# eth_part.net
KiCad netlist of a schematic drawn in Altium Designer
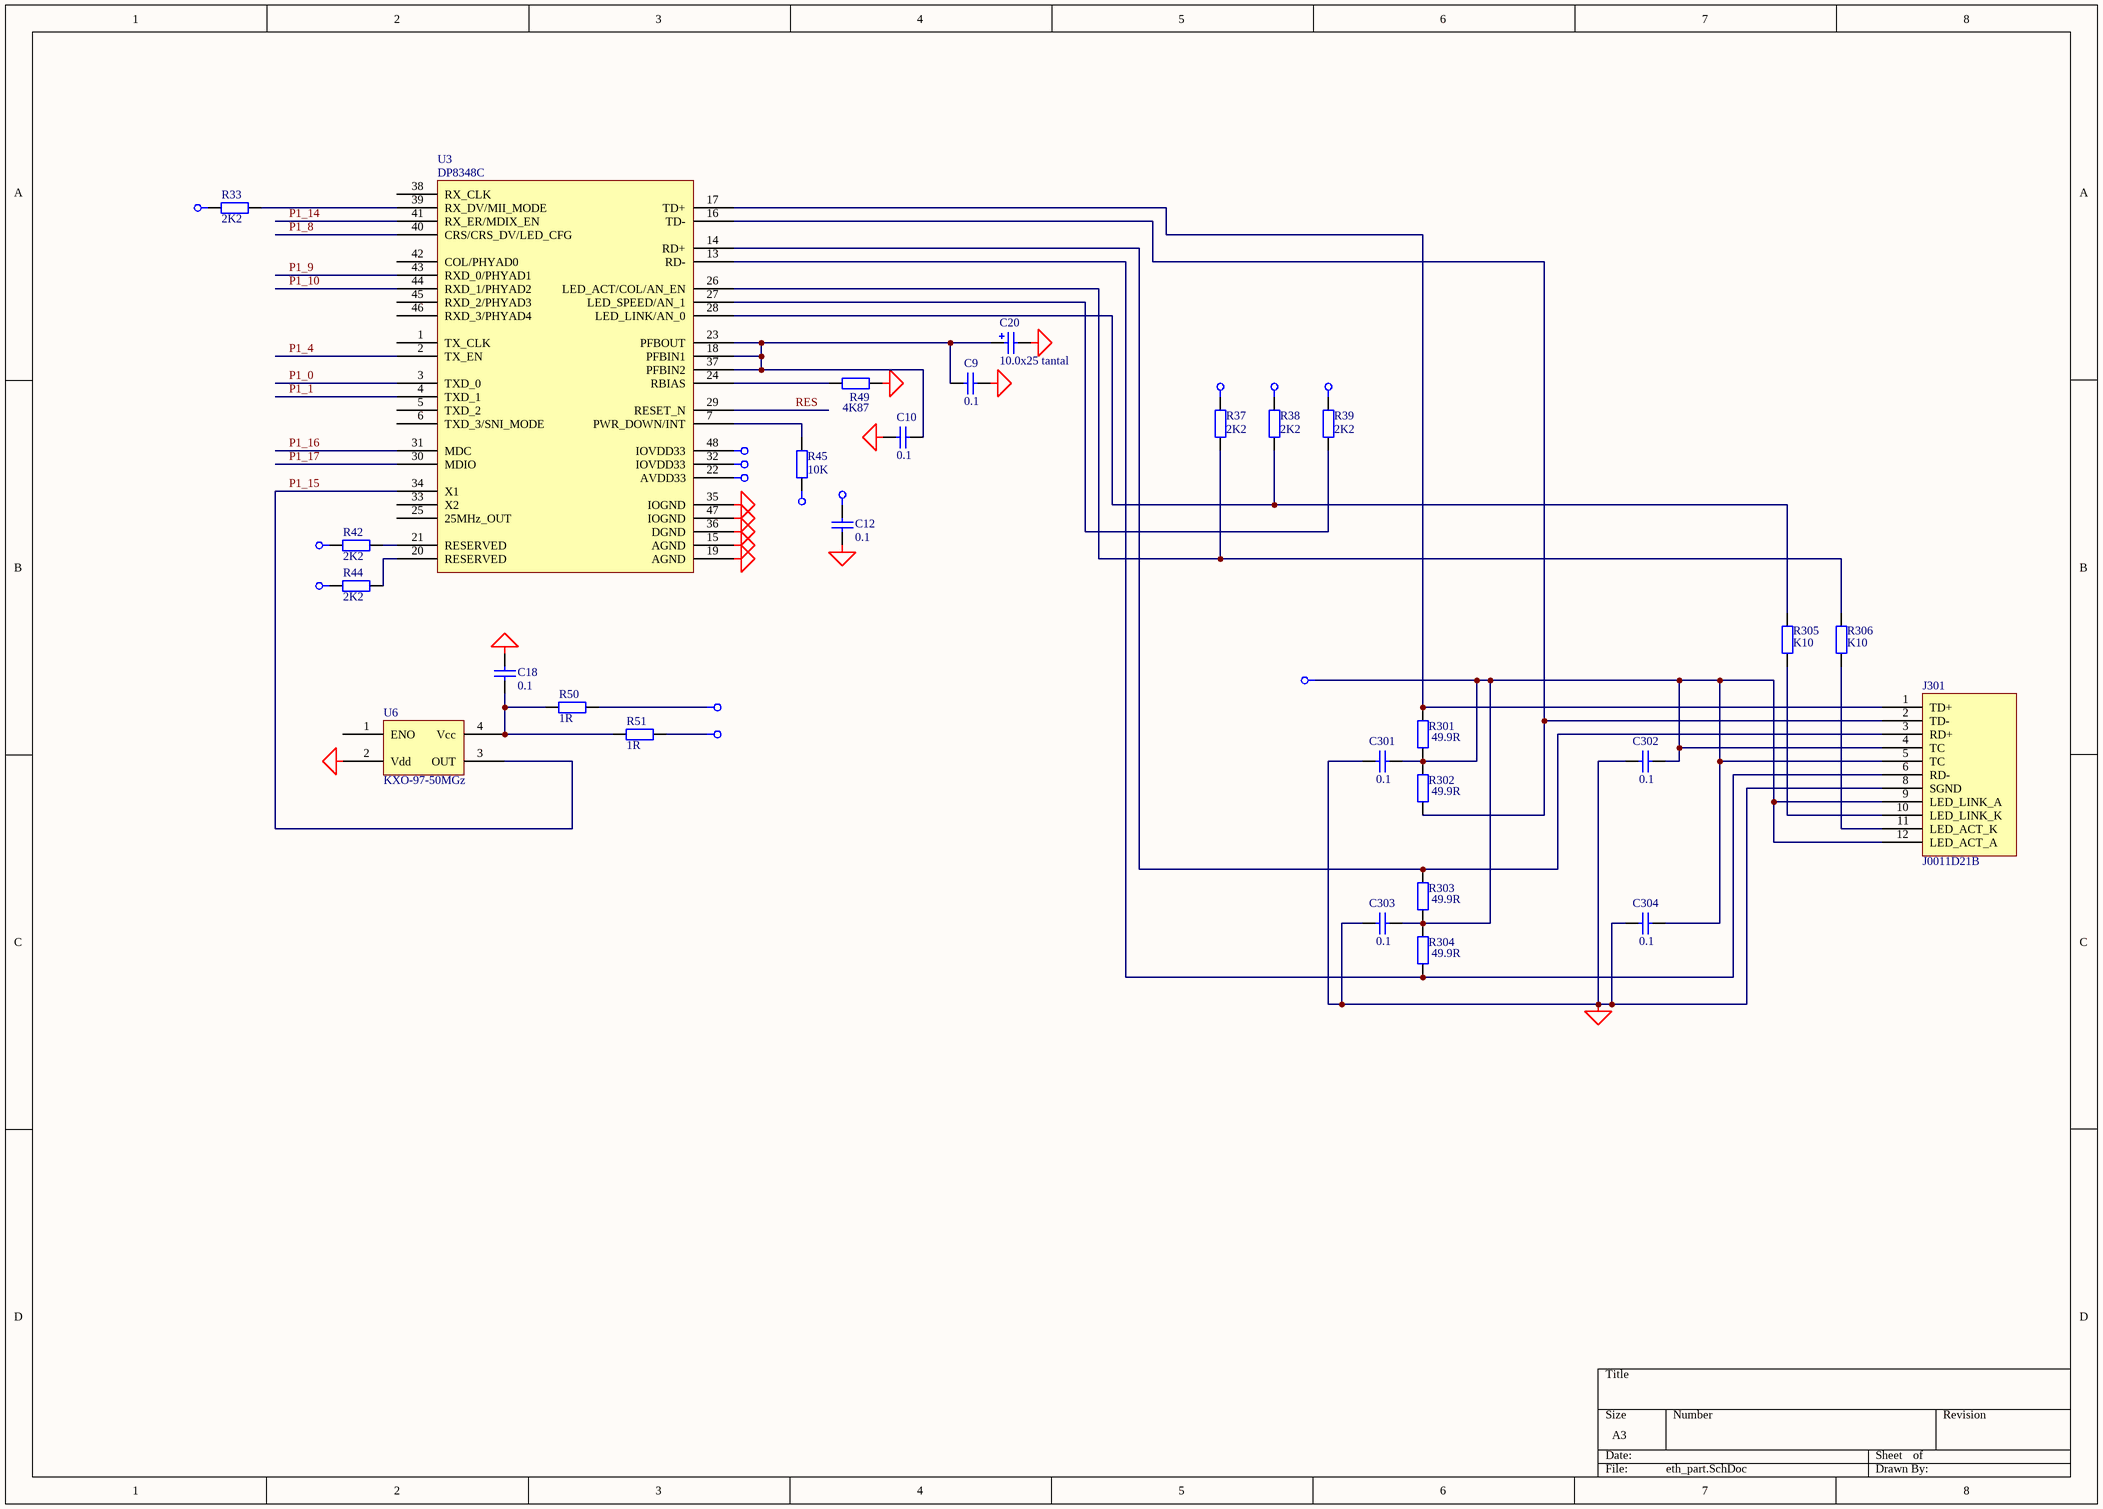
[diagram p0: eth_part.SchDoc]

(export (version "E")
  (design (tool "Eeschema 10.0.6"))
  (components
    (comp (ref "C9")
      (value "0.1")
      (footprint "C3216-1206")
      (description "Capacitor (Semiconductor SIM Model)")
      (fields (field (name "MANUFACTURER") "Generic Components") (field (name "PUBLISHER") "Altium Limited"))
      (libsource (lib "Miscellaneous Devices") (part "Cap Semi"))
    )
    (comp (ref "C10")
      (value "0.1")
      (footprint "C3216-1206")
      (description "Capacitor (Semiconductor SIM Model)")
      (fields (field (name "MANUFACTURER") "Generic Components") (field (name "PUBLISHER") "Altium Limited"))
      (libsource (lib "Miscellaneous Devices") (part "Cap Semi"))
    )
    (comp (ref "C12")
      (value "0.1")
      (footprint "_1206")
      (description "Capacitor (Semiconductor SIM Model)")
      (fields (field (name "MANUFACTURER") "Generic Components") (field (name "PUBLISHER") "Altium Limited"))
      (libsource (lib "Miscellaneous Devices") (part "Cap Semi"))
    )
    (comp (ref "C18")
      (value "0.1")
      (footprint "_1206")
      (description "Capacitor (Semiconductor SIM Model)")
      (fields (field (name "MANUFACTURER") "Generic Components") (field (name "PUBLISHER") "Altium Limited"))
      (libsource (lib "Miscellaneous Devices") (part "Cap Semi"))
    )
    (comp (ref "C20")
      (value "10.0x25 tantal")
      (footprint "CAP_EL_6_3")
      (description "Polarized Capacitor (Radial)")
      (fields (field (name "MANUFACTURER") "Generic Components") (field (name "PUBLISHER") "Altium Limited"))
      (libsource (lib "PAL") (part "Cap Pol1"))
    )
    (comp (ref "C301")
      (value "0.1")
      (footprint "C3216-1206")
      (description "Capacitor (Semiconductor SIM Model)")
      (fields (field (name "MANUFACTURER") "Generic Components") (field (name "PUBLISHER") "Altium Limited"))
      (libsource (lib "Miscellaneous Devices") (part "Cap Semi"))
    )
    (comp (ref "C302")
      (value "0.1")
      (footprint "C3216-1206")
      (description "Capacitor (Semiconductor SIM Model)")
      (fields (field (name "MANUFACTURER") "Generic Components") (field (name "PUBLISHER") "Altium Limited"))
      (libsource (lib "Miscellaneous Devices") (part "Cap Semi"))
    )
    (comp (ref "C303")
      (value "0.1")
      (footprint "C3216-1206")
      (description "Capacitor (Semiconductor SIM Model)")
      (fields (field (name "MANUFACTURER") "Generic Components") (field (name "PUBLISHER") "Altium Limited"))
      (libsource (lib "Miscellaneous Devices") (part "Cap Semi"))
    )
    (comp (ref "C304")
      (value "0.1")
      (footprint "C3216-1206")
      (description "Capacitor (Semiconductor SIM Model)")
      (fields (field (name "MANUFACTURER") "Generic Components") (field (name "PUBLISHER") "Altium Limited"))
      (libsource (lib "Miscellaneous Devices") (part "Cap Semi"))
    )
    (comp (ref "J301") (value "J0011D21B") (footprint "J0011D21B") (libsource (lib "PAL") (part "J0011D21B")))
    (comp (ref "R33")
      (value "2K2")
      (footprint "_1206")
      (description "Resistor")
      (fields (field (name "MANUFACTURER") "Generic Components") (field (name "PUBLISHER") "Altium Limited"))
      (libsource (lib "") (part "Res2_2"))
    )
    (comp (ref "R37")
      (value "2K2")
      (footprint "_1206")
      (description "Resistor")
      (fields (field (name "MANUFACTURER") "Generic Components") (field (name "PUBLISHER") "Altium Limited"))
      (libsource (lib "") (part "Res2_1"))
    )
    (comp (ref "R38")
      (value "2K2")
      (footprint "_1206")
      (description "Resistor")
      (fields (field (name "MANUFACTURER") "Generic Components") (field (name "PUBLISHER") "Altium Limited"))
      (libsource (lib "") (part "Res2_1"))
    )
    (comp (ref "R39")
      (value "2K2")
      (footprint "_1206")
      (description "Resistor")
      (fields (field (name "MANUFACTURER") "Generic Components") (field (name "PUBLISHER") "Altium Limited"))
      (libsource (lib "") (part "Res2_1"))
    )
    (comp (ref "R42")
      (value "2K2")
      (footprint "_1206")
      (description "Resistor")
      (fields (field (name "MANUFACTURER") "Generic Components") (field (name "PUBLISHER") "Altium Limited"))
      (libsource (lib "") (part "Res2_2"))
    )
    (comp (ref "R44")
      (value "2K2")
      (footprint "_1206")
      (description "Resistor")
      (fields (field (name "MANUFACTURER") "Generic Components") (field (name "PUBLISHER") "Altium Limited"))
      (libsource (lib "") (part "Res2_2"))
    )
    (comp (ref "R45")
      (value "10K")
      (footprint "_1206")
      (description "Resistor")
      (fields (field (name "MANUFACTURER") "Generic Components") (field (name "PUBLISHER") "Altium Limited"))
      (libsource (lib "Miscellaneous Devices") (part "Res2"))
    )
    (comp (ref "R49")
      (value "4K87")
      (footprint "_1206")
      (description "Resistor")
      (fields (field (name "MANUFACTURER") "Generic Components") (field (name "PUBLISHER") "Altium Limited"))
      (libsource (lib "") (part "Res2_2"))
    )
    (comp (ref "R50")
      (value "1R")
      (footprint "_1206")
      (description "Resistor")
      (fields (field (name "MANUFACTURER") "Generic Components") (field (name "PUBLISHER") "Altium Limited"))
      (libsource (lib "") (part "Res2_3"))
    )
    (comp (ref "R51")
      (value "1R")
      (footprint "_1206")
      (description "Resistor")
      (fields (field (name "MANUFACTURER") "Generic Components") (field (name "PUBLISHER") "Altium Limited"))
      (libsource (lib "") (part "Res2_3"))
    )
    (comp (ref "R301")
      (value "49.9R")
      (footprint "_1206")
      (description "Resistor")
      (fields (field (name "MANUFACTURER") "Generic Components") (field (name "PUBLISHER") "Altium Limited"))
      (libsource (lib "Miscellaneous Devices") (part "Res2"))
    )
    (comp (ref "R302")
      (value "49.9R")
      (footprint "_1206")
      (description "Resistor")
      (fields (field (name "MANUFACTURER") "Generic Components") (field (name "PUBLISHER") "Altium Limited"))
      (libsource (lib "Miscellaneous Devices") (part "Res2"))
    )
    (comp (ref "R303")
      (value "49.9R")
      (footprint "_1206")
      (description "Resistor")
      (fields (field (name "MANUFACTURER") "Generic Components") (field (name "PUBLISHER") "Altium Limited"))
      (libsource (lib "Miscellaneous Devices") (part "Res2"))
    )
    (comp (ref "R304")
      (value "49.9R")
      (footprint "_1206")
      (description "Resistor")
      (fields (field (name "MANUFACTURER") "Generic Components") (field (name "PUBLISHER") "Altium Limited"))
      (libsource (lib "Miscellaneous Devices") (part "Res2"))
    )
    (comp (ref "R305")
      (value "K10")
      (footprint "_1206")
      (description "Resistor")
      (fields (field (name "MANUFACTURER") "Generic Components") (field (name "PUBLISHER") "Altium Limited"))
      (libsource (lib "") (part "Res2_1"))
    )
    (comp (ref "R306")
      (value "K10")
      (footprint "_1206")
      (description "Resistor")
      (fields (field (name "MANUFACTURER") "Generic Components") (field (name "PUBLISHER") "Altium Limited"))
      (libsource (lib "") (part "Res2_1"))
    )
    (comp (ref "U3") (value "DP8348C") (footprint "F-QFP7X7-G48/N") (libsource (lib "PAL") (part "DP8348C")))
    (comp (ref "U6") (value "KXO-97-50MGz") (footprint "KXO-97") (libsource (lib "PAL") (part "KXO-97")))
  )
  (nets
    (net (code "1") (name "+3v3") (class "Default")
      (node (ref "C12") (pin "1") (pinfunction "1_1") (pintype "passive"))
      (node (ref "C301") (pin "2") (pinfunction "2_2") (pintype "passive"))
      (node (ref "C302") (pin "2") (pinfunction "2_2") (pintype "passive"))
      (node (ref "C303") (pin "2") (pinfunction "2_2") (pintype "passive"))
      (node (ref "C304") (pin "2") (pinfunction "2_2") (pintype "passive"))
      (node (ref "J301") (pin "12") (pinfunction "LED_ACT_A_12") (pintype "passive"))
      (node (ref "J301") (pin "4") (pinfunction "TC_4") (pintype "passive"))
      (node (ref "J301") (pin "5") (pinfunction "TC_5") (pintype "passive"))
      (node (ref "J301") (pin "9") (pinfunction "LED_LINK_A_9") (pintype "passive"))
      (node (ref "R301") (pin "2") (pinfunction "2_2") (pintype "passive"))
      (node (ref "R302") (pin "1") (pinfunction "1_1") (pintype "passive"))
      (node (ref "R303") (pin "2") (pinfunction "2_2") (pintype "passive"))
      (node (ref "R304") (pin "1") (pinfunction "1_1") (pintype "passive"))
      (node (ref "R33") (pin "2") (pinfunction "2_2") (pintype "passive"))
      (node (ref "R37") (pin "2") (pinfunction "2_2") (pintype "passive"))
      (node (ref "R38") (pin "2") (pinfunction "2_2") (pintype "passive"))
      (node (ref "R39") (pin "2") (pinfunction "2_2") (pintype "passive"))
      (node (ref "R42") (pin "2") (pinfunction "2_2") (pintype "passive"))
      (node (ref "R44") (pin "2") (pinfunction "2_2") (pintype "passive"))
      (node (ref "R45") (pin "2") (pinfunction "2_2") (pintype "passive"))
      (node (ref "R51") (pin "2") (pinfunction "2_2") (pintype "passive"))
      (node (ref "U3") (pin "22") (pinfunction "AVDD33_22") (pintype "passive"))
      (node (ref "U3") (pin "32") (pinfunction "IOVDD33_32") (pintype "passive"))
      (node (ref "U3") (pin "48") (pinfunction "IOVDD33_48") (pintype "passive"))
    )
    (net (code "2") (name "+5v") (class "Default")
      (node (ref "R50") (pin "2") (pinfunction "2_2") (pintype "passive"))
    )
    (net (code "3") (name "/P1_0") (class "Default")
      (node (ref "U3") (pin "3") (pinfunction "TXD_0_3") (pintype "passive"))
    )
    (net (code "4") (name "/P1_1") (class "Default")
      (node (ref "U3") (pin "4") (pinfunction "TXD_1_4") (pintype "passive"))
    )
    (net (code "5") (name "/P1_4") (class "Default")
      (node (ref "U3") (pin "2") (pinfunction "TX_EN_2") (pintype "passive"))
    )
    (net (code "6") (name "/P1_8") (class "Default")
      (node (ref "U3") (pin "40") (pinfunction "CRS/CRS_DV/LED_CFG_40") (pintype "passive"))
    )
    (net (code "7") (name "/P1_9") (class "Default")
      (node (ref "U3") (pin "43") (pinfunction "RXD_0/PHYAD1_43") (pintype "passive"))
    )
    (net (code "8") (name "/P1_10") (class "Default")
      (node (ref "U3") (pin "44") (pinfunction "RXD_1/PHYAD2_44") (pintype "passive"))
    )
    (net (code "9") (name "/P1_14") (class "Default")
      (node (ref "U3") (pin "41") (pinfunction "RX_ER/MDIX_EN_41") (pintype "passive"))
    )
    (net (code "10") (name "/P1_15") (class "Default")
      (node (ref "U3") (pin "34") (pinfunction "X1_34") (pintype "passive"))
      (node (ref "U6") (pin "3") (pinfunction "OUT_3") (pintype "passive"))
    )
    (net (code "11") (name "/P1_16") (class "Default")
      (node (ref "U3") (pin "31") (pinfunction "MDC_31") (pintype "passive"))
    )
    (net (code "12") (name "/P1_17") (class "Default")
      (node (ref "U3") (pin "30") (pinfunction "MDIO_30") (pintype "passive"))
    )
    (net (code "13") (name "/RES") (class "Default")
      (node (ref "U3") (pin "29") (pinfunction "RESET_N_29") (pintype "passive"))
    )
    (net (code "14") (name "GND") (class "Default")
      (node (ref "C10") (pin "2") (pinfunction "2_2") (pintype "passive"))
      (node (ref "C12") (pin "2") (pinfunction "2_2") (pintype "passive"))
      (node (ref "C18") (pin "2") (pinfunction "2_2") (pintype "passive"))
      (node (ref "C20") (pin "2") (pinfunction "2_2") (pintype "passive"))
      (node (ref "C301") (pin "1") (pinfunction "1_1") (pintype "passive"))
      (node (ref "C302") (pin "1") (pinfunction "1_1") (pintype "passive"))
      (node (ref "C303") (pin "1") (pinfunction "1_1") (pintype "passive"))
      (node (ref "C304") (pin "1") (pinfunction "1_1") (pintype "passive"))
      (node (ref "C9") (pin "2") (pinfunction "2_2") (pintype "passive"))
      (node (ref "J301") (pin "8") (pinfunction "SGND_8") (pintype "passive"))
      (node (ref "R49") (pin "1") (pinfunction "1_1") (pintype "passive"))
      (node (ref "U3") (pin "15") (pinfunction "AGND_15") (pintype "passive"))
      (node (ref "U3") (pin "19") (pinfunction "AGND_19") (pintype "passive"))
      (node (ref "U3") (pin "35") (pinfunction "IOGND_35") (pintype "passive"))
      (node (ref "U3") (pin "36") (pinfunction "DGND_36") (pintype "passive"))
      (node (ref "U3") (pin "47") (pinfunction "IOGND_47") (pintype "passive"))
      (node (ref "U6") (pin "2") (pinfunction "Vdd_2") (pintype "passive"))
    )
    (net (code "15") (name "Net-(J301-LED_ACT_K)") (class "Default")
      (node (ref "J301") (pin "11") (pinfunction "LED_ACT_K_11") (pintype "passive"))
      (node (ref "R306") (pin "1") (pinfunction "1_1") (pintype "passive"))
    )
    (net (code "16") (name "Net-(J301-LED_LINK_K)") (class "Default")
      (node (ref "J301") (pin "10") (pinfunction "LED_LINK_K_10") (pintype "passive"))
      (node (ref "R305") (pin "1") (pinfunction "1_1") (pintype "passive"))
    )
    (net (code "17") (name "Net-(J301-RD+)") (class "Default")
      (node (ref "J301") (pin "3") (pinfunction "RD+_3") (pintype "passive"))
      (node (ref "R303") (pin "1") (pinfunction "1_1") (pintype "passive"))
      (node (ref "U3") (pin "14") (pinfunction "RD+_14") (pintype "passive"))
    )
    (net (code "18") (name "Net-(J301-RD-)") (class "Default")
      (node (ref "J301") (pin "6") (pinfunction "RD-_6") (pintype "passive"))
      (node (ref "R304") (pin "2") (pinfunction "2_2") (pintype "passive"))
      (node (ref "U3") (pin "13") (pinfunction "RD-_13") (pintype "passive"))
    )
    (net (code "19") (name "Net-(J301-TD+)") (class "Default")
      (node (ref "J301") (pin "1") (pinfunction "TD+_1") (pintype "passive"))
      (node (ref "R301") (pin "1") (pinfunction "1_1") (pintype "passive"))
      (node (ref "U3") (pin "17") (pinfunction "TD+_17") (pintype "passive"))
    )
    (net (code "20") (name "Net-(J301-TD-)") (class "Default")
      (node (ref "J301") (pin "2") (pinfunction "TD-_2") (pintype "passive"))
      (node (ref "R302") (pin "2") (pinfunction "2_2") (pintype "passive"))
      (node (ref "U3") (pin "16") (pinfunction "TD-_16") (pintype "passive"))
    )
    (net (code "21") (name "Net-(R42-Pad1)") (class "Default")
      (node (ref "R42") (pin "1") (pinfunction "1_1") (pintype "passive"))
      (node (ref "U3") (pin "21") (pinfunction "RESERVED_21") (pintype "passive"))
    )
    (net (code "22") (name "Net-(R44-Pad1)") (class "Default")
      (node (ref "R44") (pin "1") (pinfunction "1_1") (pintype "passive"))
      (node (ref "U3") (pin "20") (pinfunction "RESERVED_20") (pintype "passive"))
    )
    (net (code "23") (name "Net-(U3-LED_ACT{slash}COL{slash}AN_EN)") (class "Default")
      (node (ref "R306") (pin "2") (pinfunction "2_2") (pintype "passive"))
      (node (ref "R37") (pin "1") (pinfunction "1_1") (pintype "passive"))
      (node (ref "U3") (pin "26") (pinfunction "LED_ACT/COL/AN_EN_26") (pintype "passive"))
    )
    (net (code "24") (name "Net-(U3-LED_LINK{slash}AN_0)") (class "Default")
      (node (ref "R305") (pin "2") (pinfunction "2_2") (pintype "passive"))
      (node (ref "R38") (pin "1") (pinfunction "1_1") (pintype "passive"))
      (node (ref "U3") (pin "28") (pinfunction "LED_LINK/AN_0_28") (pintype "passive"))
    )
    (net (code "25") (name "Net-(U3-LED_SPEED{slash}AN_1)") (class "Default")
      (node (ref "R39") (pin "1") (pinfunction "1_1") (pintype "passive"))
      (node (ref "U3") (pin "27") (pinfunction "LED_SPEED/AN_1_27") (pintype "passive"))
    )
    (net (code "26") (name "Net-(U3-PFBIN1)") (class "Default")
      (node (ref "C10") (pin "1") (pinfunction "1_1") (pintype "passive"))
      (node (ref "C20") (pin "1") (pinfunction "1_1") (pintype "passive"))
      (node (ref "C9") (pin "1") (pinfunction "1_1") (pintype "passive"))
      (node (ref "U3") (pin "18") (pinfunction "PFBIN1_18") (pintype "passive"))
      (node (ref "U3") (pin "23") (pinfunction "PFBOUT_23") (pintype "passive"))
      (node (ref "U3") (pin "37") (pinfunction "PFBIN2_37") (pintype "passive"))
    )
    (net (code "27") (name "Net-(U3-PWR_DOWN{slash}INT)") (class "Default")
      (node (ref "R45") (pin "1") (pinfunction "1_1") (pintype "passive"))
      (node (ref "U3") (pin "7") (pinfunction "PWR_DOWN/INT_7") (pintype "passive"))
    )
    (net (code "28") (name "Net-(U3-RBIAS)") (class "Default")
      (node (ref "R49") (pin "2") (pinfunction "2_2") (pintype "passive"))
      (node (ref "U3") (pin "24") (pinfunction "RBIAS_24") (pintype "passive"))
    )
    (net (code "29") (name "Net-(U3-RX_DV{slash}MII_MODE)") (class "Default")
      (node (ref "R33") (pin "1") (pinfunction "1_1") (pintype "passive"))
      (node (ref "U3") (pin "39") (pinfunction "RX_DV/MII_MODE_39") (pintype "passive"))
    )
    (net (code "30") (name "Net-(U6-Vcc)") (class "Default")
      (node (ref "C18") (pin "1") (pinfunction "1_1") (pintype "passive"))
      (node (ref "R50") (pin "1") (pinfunction "1_1") (pintype "passive"))
      (node (ref "R51") (pin "1") (pinfunction "1_1") (pintype "passive"))
      (node (ref "U6") (pin "4") (pinfunction "Vcc_4") (pintype "passive"))
    )
    (net (code "31") (name "unconnected-(U3-25MHz_OUT-Pad25)") (class "Default")
      (node (ref "U3") (pin "25") (pinfunction "25MHz_OUT_25") (pintype "passive"))
    )
    (net (code "32") (name "unconnected-(U3-COL{slash}PHYAD0-Pad42)") (class "Default")
      (node (ref "U3") (pin "42") (pinfunction "COL/PHYAD0_42") (pintype "passive"))
    )
    (net (code "33") (name "unconnected-(U3-RXD_2{slash}PHYAD3-Pad45)") (class "Default")
      (node (ref "U3") (pin "45") (pinfunction "RXD_2/PHYAD3_45") (pintype "passive"))
    )
    (net (code "34") (name "unconnected-(U3-RXD_3{slash}PHYAD4-Pad46)") (class "Default")
      (node (ref "U3") (pin "46") (pinfunction "RXD_3/PHYAD4_46") (pintype "passive"))
    )
    (net (code "35") (name "unconnected-(U3-RX_CLK-Pad38)") (class "Default")
      (node (ref "U3") (pin "38") (pinfunction "RX_CLK_38") (pintype "passive"))
    )
    (net (code "36") (name "unconnected-(U3-TXD_2-Pad5)") (class "Default")
      (node (ref "U3") (pin "5") (pinfunction "TXD_2_5") (pintype "passive"))
    )
    (net (code "37") (name "unconnected-(U3-TXD_3{slash}SNI_MODE-Pad6)") (class "Default")
      (node (ref "U3") (pin "6") (pinfunction "TXD_3/SNI_MODE_6") (pintype "passive"))
    )
    (net (code "38") (name "unconnected-(U3-TX_CLK-Pad1)") (class "Default")
      (node (ref "U3") (pin "1") (pinfunction "TX_CLK_1") (pintype "passive"))
    )
    (net (code "39") (name "unconnected-(U3-X2-Pad33)") (class "Default")
      (node (ref "U3") (pin "33") (pinfunction "X2_33") (pintype "passive"))
    )
    (net (code "40") (name "unconnected-(U6-ENO-Pad1)") (class "Default")
      (node (ref "U6") (pin "1") (pinfunction "ENO_1") (pintype "passive"))
    )
  )
)
